# hexapod.net
KiCad netlist of a schematic drawn in EAGLE
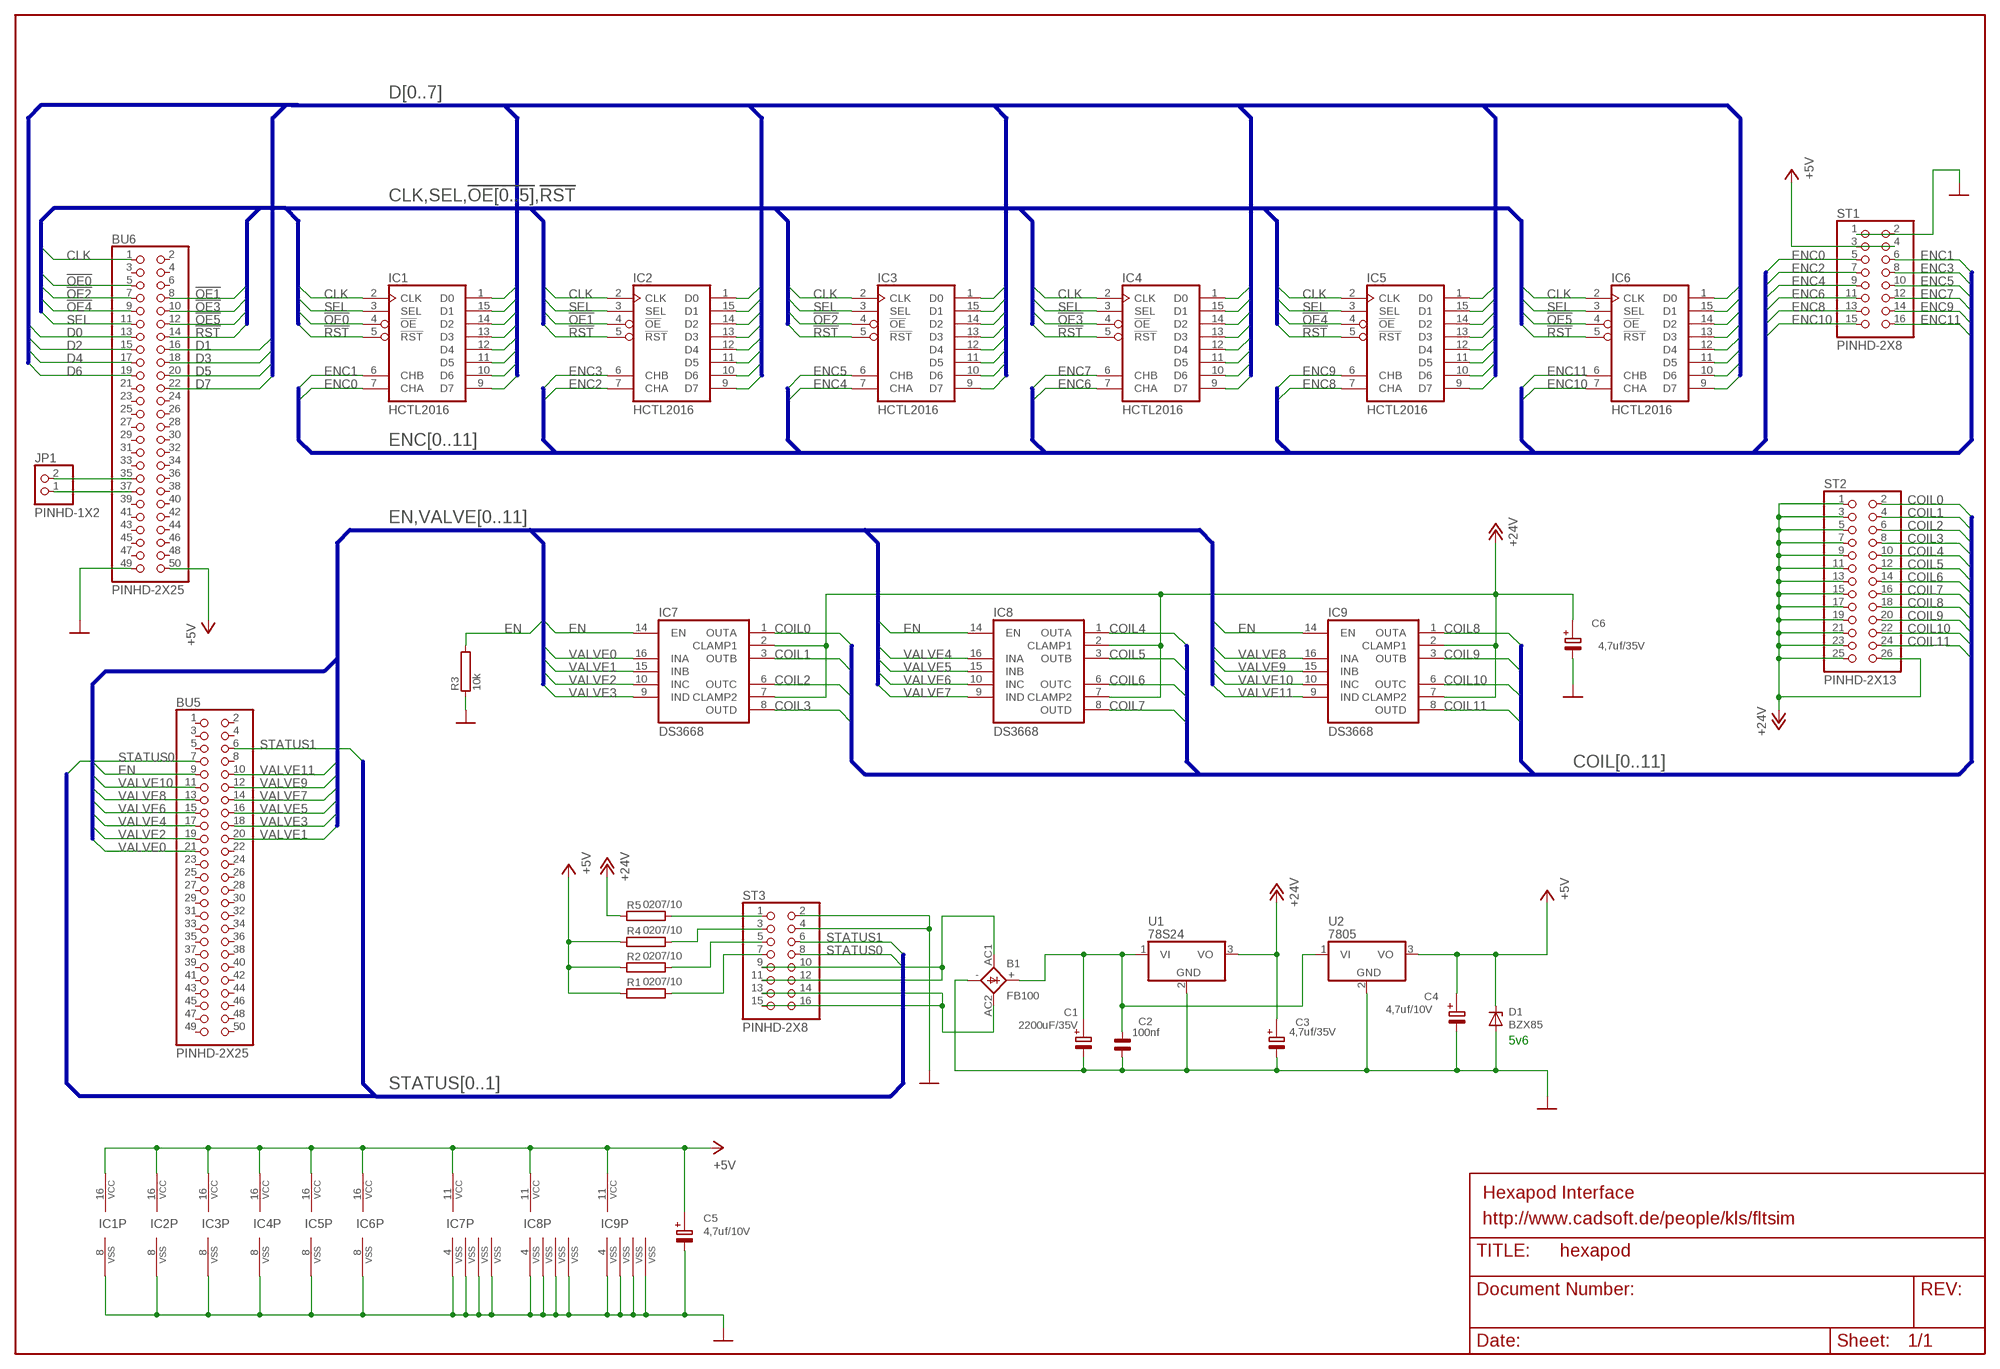
[diagram p0: schematic, sheet 1]

(export (version "E")
  (design (tool "Eeschema 10.0.6"))
  (components
    (comp (ref "B1")
      (value "FB100")
      (footprint "eagle-import:FB100")
      (libsource (lib "eagle-import") (part "FB100"))
    )
    (comp (ref "BU5")
      (value "PINHD-2X25")
      (footprint "eagle-import:2X25")
      (libsource (lib "eagle-import") (part "PINHD-2X25"))
    )
    (comp (ref "BU6")
      (value "PINHD-2X25")
      (footprint "eagle-import:2X25")
      (libsource (lib "eagle-import") (part "PINHD-2X25"))
    )
    (comp (ref "C1")
      (value "2200uF/35V")
      (footprint "eagle-import:E35-16")
      (libsource (lib "eagle-import") (part "E35-16"))
    )
    (comp (ref "C2")
      (value "100nf")
      (footprint "eagle-import:C5B2,5A")
      (libsource (lib "eagle-import") (part "C5B2,5A"))
    )
    (comp (ref "C3")
      (value "4,7uf/35V")
      (footprint "eagle-import:E2,5-5")
      (libsource (lib "eagle-import") (part "E2-5@1"))
    )
    (comp (ref "C4")
      (value "4,7uf/10V")
      (footprint "eagle-import:E2,5-5")
      (libsource (lib "eagle-import") (part "E2,5-5"))
    )
    (comp (ref "C5")
      (value "4,7uf/10V")
      (footprint "eagle-import:E2,5-5")
      (libsource (lib "eagle-import") (part "E2,5-5"))
    )
    (comp (ref "C6")
      (value "4,7uf/35V")
      (footprint "eagle-import:E2,5-5")
      (libsource (lib "eagle-import") (part "E2-5@1"))
    )
    (comp (ref "D1")
      (value "BZX85")
      (footprint "eagle-import:DO41Z10")
      (libsource (lib "eagle-import") (part "BZX85"))
    )
    (comp (ref "IC1")
      (value "HCTL2016")
      (footprint "eagle-import:DIL-16")
      (libsource (lib "eagle-import") (part "HCTL2016"))
    )
    (comp (ref "IC2")
      (value "HCTL2016")
      (footprint "eagle-import:DIL-16")
      (libsource (lib "eagle-import") (part "HCTL2016"))
    )
    (comp (ref "IC3")
      (value "HCTL2016")
      (footprint "eagle-import:DIL-16")
      (libsource (lib "eagle-import") (part "HCTL2016"))
    )
    (comp (ref "IC4")
      (value "HCTL2016")
      (footprint "eagle-import:DIL-16")
      (libsource (lib "eagle-import") (part "HCTL2016"))
    )
    (comp (ref "IC5")
      (value "HCTL2016")
      (footprint "eagle-import:DIL-16")
      (libsource (lib "eagle-import") (part "HCTL2016"))
    )
    (comp (ref "IC6")
      (value "HCTL2016")
      (footprint "eagle-import:DIL-16")
      (libsource (lib "eagle-import") (part "HCTL2016"))
    )
    (comp (ref "IC7")
      (value "DS3668")
      (footprint "eagle-import:DIL-16")
      (libsource (lib "eagle-import") (part "DS3668"))
    )
    (comp (ref "IC8")
      (value "DS3668")
      (footprint "eagle-import:DIL-16")
      (libsource (lib "eagle-import") (part "DS3668"))
    )
    (comp (ref "IC9")
      (value "DS3668")
      (footprint "eagle-import:DIL-16")
      (libsource (lib "eagle-import") (part "DS3668"))
    )
    (comp (ref "JP1")
      (value "PINHD-1X2")
      (footprint "eagle-import:1X02")
      (libsource (lib "eagle-import") (part "PINHD-1X2"))
    )
    (comp (ref "R1")
      (value "0207/10")
      (footprint "eagle-import:0207_10")
      (libsource (lib "eagle-import") (part "0207/10"))
    )
    (comp (ref "R2")
      (value "0207/10")
      (footprint "eagle-import:0207_10")
      (libsource (lib "eagle-import") (part "0207/10"))
    )
    (comp (ref "R3")
      (value "10k")
      (footprint "eagle-import:0207_10@1")
      (libsource (lib "eagle-import") (part "0207/10@1"))
    )
    (comp (ref "R4")
      (value "0207/10")
      (footprint "eagle-import:0207_10")
      (libsource (lib "eagle-import") (part "0207/10"))
    )
    (comp (ref "R5")
      (value "0207/10")
      (footprint "eagle-import:0207_10")
      (libsource (lib "eagle-import") (part "0207/10"))
    )
    (comp (ref "ST1")
      (value "PINHD-2X8")
      (footprint "eagle-import:ML16")
      (libsource (lib "eagle-import") (part "PINHD-2X8@1"))
    )
    (comp (ref "ST2")
      (value "PINHD-2X13")
      (footprint "eagle-import:ML26")
      (libsource (lib "eagle-import") (part "PINHD-2X13@1"))
    )
    (comp (ref "ST3")
      (value "PINHD-2X8")
      (footprint "eagle-import:ML16")
      (libsource (lib "eagle-import") (part "PINHD-2X8@1"))
    )
    (comp (ref "U1")
      (value "78S24")
      (footprint "eagle-import:TO220H")
      (libsource (lib "eagle-import") (part "78XXT"))
    )
    (comp (ref "U2")
      (value "7805")
      (footprint "eagle-import:TO220H")
      (libsource (lib "eagle-import") (part "78XXT"))
    )
  )
  (nets
    (net (code "13") (name "+5V") (class "Default")
      (node (ref "BU6") (pin "50") (pinfunction "50_50") (pintype "passive"))
      (node (ref "C4") (pin "+") (pinfunction "+_+") (pintype "passive"))
      (node (ref "C5") (pin "+") (pinfunction "+_+") (pintype "passive"))
      (node (ref "D1") (pin "K") (pinfunction "K_K") (pintype "passive"))
      (node (ref "IC1") (pin "16") (pinfunction "VCC_16") (pintype "power_in"))
      (node (ref "IC2") (pin "16") (pinfunction "VCC_16") (pintype "power_in"))
      (node (ref "IC3") (pin "16") (pinfunction "VCC_16") (pintype "power_in"))
      (node (ref "IC4") (pin "16") (pinfunction "VCC_16") (pintype "power_in"))
      (node (ref "IC5") (pin "16") (pinfunction "VCC_16") (pintype "power_in"))
      (node (ref "IC6") (pin "16") (pinfunction "VCC_16") (pintype "power_in"))
      (node (ref "IC7") (pin "11") (pinfunction "VCC_11") (pintype "power_in"))
      (node (ref "IC8") (pin "11") (pinfunction "VCC_11") (pintype "power_in"))
      (node (ref "IC9") (pin "11") (pinfunction "VCC_11") (pintype "power_in"))
      (node (ref "R1") (pin "1") (pinfunction "1_1") (pintype "passive"))
      (node (ref "R2") (pin "1") (pinfunction "1_1") (pintype "passive"))
      (node (ref "R4") (pin "1") (pinfunction "1_1") (pintype "passive"))
      (node (ref "ST1") (pin "3") (pinfunction "3_3") (pintype "passive"))
      (node (ref "ST1") (pin "4") (pinfunction "4_4") (pintype "passive"))
      (node (ref "U2") (pin "3") (pinfunction "VO_3") (pintype "output"))
    )
    (net (code "14") (name "+24V") (class "Default")
      (node (ref "C3") (pin "+") (pinfunction "+_+") (pintype "passive"))
      (node (ref "C6") (pin "+") (pinfunction "+_+") (pintype "passive"))
      (node (ref "IC7") (pin "2") (pinfunction "CLAMP1_2") (pintype "bidirectional"))
      (node (ref "IC7") (pin "7") (pinfunction "CLAMP2_7") (pintype "bidirectional"))
      (node (ref "IC8") (pin "2") (pinfunction "CLAMP1_2") (pintype "bidirectional"))
      (node (ref "IC8") (pin "7") (pinfunction "CLAMP2_7") (pintype "bidirectional"))
      (node (ref "IC9") (pin "2") (pinfunction "CLAMP1_2") (pintype "bidirectional"))
      (node (ref "IC9") (pin "7") (pinfunction "CLAMP2_7") (pintype "bidirectional"))
      (node (ref "R5") (pin "1") (pinfunction "1_1") (pintype "passive"))
      (node (ref "ST2") (pin "1") (pinfunction "1_1") (pintype "passive"))
      (node (ref "ST2") (pin "11") (pinfunction "11_11") (pintype "passive"))
      (node (ref "ST2") (pin "13") (pinfunction "13_13") (pintype "passive"))
      (node (ref "ST2") (pin "15") (pinfunction "15_15") (pintype "passive"))
      (node (ref "ST2") (pin "17") (pinfunction "17_17") (pintype "passive"))
      (node (ref "ST2") (pin "19") (pinfunction "19_19") (pintype "passive"))
      (node (ref "ST2") (pin "21") (pinfunction "21_21") (pintype "passive"))
      (node (ref "ST2") (pin "23") (pinfunction "23_23") (pintype "passive"))
      (node (ref "ST2") (pin "25") (pinfunction "25_25") (pintype "passive"))
      (node (ref "ST2") (pin "26") (pinfunction "26_26") (pintype "passive"))
      (node (ref "ST2") (pin "3") (pinfunction "3_3") (pintype "passive"))
      (node (ref "ST2") (pin "5") (pinfunction "5_5") (pintype "passive"))
      (node (ref "ST2") (pin "7") (pinfunction "7_7") (pintype "passive"))
      (node (ref "ST2") (pin "9") (pinfunction "9_9") (pintype "passive"))
      (node (ref "U1") (pin "3") (pinfunction "VO_3") (pintype "output"))
    )
    (net (code "15") (name "/CLK") (class "Default")
      (node (ref "BU6") (pin "1") (pinfunction "1_1") (pintype "passive"))
      (node (ref "IC1") (pin "2") (pinfunction "CLK_2") (pintype "input"))
      (node (ref "IC2") (pin "2") (pinfunction "CLK_2") (pintype "input"))
      (node (ref "IC3") (pin "2") (pinfunction "CLK_2") (pintype "input"))
      (node (ref "IC4") (pin "2") (pinfunction "CLK_2") (pintype "input"))
      (node (ref "IC5") (pin "2") (pinfunction "CLK_2") (pintype "input"))
      (node (ref "IC6") (pin "2") (pinfunction "CLK_2") (pintype "input"))
    )
    (net (code "16") (name "/COIL0") (class "Default")
      (node (ref "IC7") (pin "1") (pinfunction "OUTA_1") (pintype "bidirectional"))
      (node (ref "ST2") (pin "2") (pinfunction "2_2") (pintype "passive"))
    )
    (net (code "17") (name "/COIL1") (class "Default")
      (node (ref "IC7") (pin "3") (pinfunction "OUTB_3") (pintype "bidirectional"))
      (node (ref "ST2") (pin "4") (pinfunction "4_4") (pintype "passive"))
    )
    (net (code "18") (name "/COIL2") (class "Default")
      (node (ref "IC7") (pin "6") (pinfunction "OUTC_6") (pintype "bidirectional"))
      (node (ref "ST2") (pin "6") (pinfunction "6_6") (pintype "passive"))
    )
    (net (code "19") (name "/COIL3") (class "Default")
      (node (ref "IC7") (pin "8") (pinfunction "OUTD_8") (pintype "bidirectional"))
      (node (ref "ST2") (pin "8") (pinfunction "8_8") (pintype "passive"))
    )
    (net (code "20") (name "/COIL4") (class "Default")
      (node (ref "IC8") (pin "1") (pinfunction "OUTA_1") (pintype "bidirectional"))
      (node (ref "ST2") (pin "10") (pinfunction "10_10") (pintype "passive"))
    )
    (net (code "21") (name "/COIL5") (class "Default")
      (node (ref "IC8") (pin "3") (pinfunction "OUTB_3") (pintype "bidirectional"))
      (node (ref "ST2") (pin "12") (pinfunction "12_12") (pintype "passive"))
    )
    (net (code "22") (name "/COIL6") (class "Default")
      (node (ref "IC8") (pin "6") (pinfunction "OUTC_6") (pintype "bidirectional"))
      (node (ref "ST2") (pin "14") (pinfunction "14_14") (pintype "passive"))
    )
    (net (code "23") (name "/COIL7") (class "Default")
      (node (ref "IC8") (pin "8") (pinfunction "OUTD_8") (pintype "bidirectional"))
      (node (ref "ST2") (pin "16") (pinfunction "16_16") (pintype "passive"))
    )
    (net (code "24") (name "/COIL8") (class "Default")
      (node (ref "IC9") (pin "1") (pinfunction "OUTA_1") (pintype "bidirectional"))
      (node (ref "ST2") (pin "18") (pinfunction "18_18") (pintype "passive"))
    )
    (net (code "25") (name "/COIL9") (class "Default")
      (node (ref "IC9") (pin "3") (pinfunction "OUTB_3") (pintype "bidirectional"))
      (node (ref "ST2") (pin "20") (pinfunction "20_20") (pintype "passive"))
    )
    (net (code "26") (name "/COIL10") (class "Default")
      (node (ref "IC9") (pin "6") (pinfunction "OUTC_6") (pintype "bidirectional"))
      (node (ref "ST2") (pin "22") (pinfunction "22_22") (pintype "passive"))
    )
    (net (code "27") (name "/COIL11") (class "Default")
      (node (ref "IC9") (pin "8") (pinfunction "OUTD_8") (pintype "bidirectional"))
      (node (ref "ST2") (pin "24") (pinfunction "24_24") (pintype "passive"))
    )
    (net (code "29") (name "/D0") (class "Default")
      (node (ref "BU6") (pin "13") (pinfunction "13_13") (pintype "passive"))
      (node (ref "IC1") (pin "1") (pinfunction "D0_1") (pintype "output"))
      (node (ref "IC2") (pin "1") (pinfunction "D0_1") (pintype "output"))
      (node (ref "IC3") (pin "1") (pinfunction "D0_1") (pintype "output"))
      (node (ref "IC4") (pin "1") (pinfunction "D0_1") (pintype "output"))
      (node (ref "IC5") (pin "1") (pinfunction "D0_1") (pintype "output"))
      (node (ref "IC6") (pin "1") (pinfunction "D0_1") (pintype "output"))
    )
    (net (code "30") (name "/D1") (class "Default")
      (node (ref "BU6") (pin "16") (pinfunction "16_16") (pintype "passive"))
      (node (ref "IC1") (pin "15") (pinfunction "D1_15") (pintype "output"))
      (node (ref "IC2") (pin "15") (pinfunction "D1_15") (pintype "output"))
      (node (ref "IC3") (pin "15") (pinfunction "D1_15") (pintype "output"))
      (node (ref "IC4") (pin "15") (pinfunction "D1_15") (pintype "output"))
      (node (ref "IC5") (pin "15") (pinfunction "D1_15") (pintype "output"))
      (node (ref "IC6") (pin "15") (pinfunction "D1_15") (pintype "output"))
    )
    (net (code "31") (name "/D2") (class "Default")
      (node (ref "BU6") (pin "15") (pinfunction "15_15") (pintype "passive"))
      (node (ref "IC1") (pin "14") (pinfunction "D2_14") (pintype "output"))
      (node (ref "IC2") (pin "14") (pinfunction "D2_14") (pintype "output"))
      (node (ref "IC3") (pin "14") (pinfunction "D2_14") (pintype "output"))
      (node (ref "IC4") (pin "14") (pinfunction "D2_14") (pintype "output"))
      (node (ref "IC5") (pin "14") (pinfunction "D2_14") (pintype "output"))
      (node (ref "IC6") (pin "14") (pinfunction "D2_14") (pintype "output"))
    )
    (net (code "32") (name "/D3") (class "Default")
      (node (ref "BU6") (pin "18") (pinfunction "18_18") (pintype "passive"))
      (node (ref "IC1") (pin "13") (pinfunction "D3_13") (pintype "output"))
      (node (ref "IC2") (pin "13") (pinfunction "D3_13") (pintype "output"))
      (node (ref "IC3") (pin "13") (pinfunction "D3_13") (pintype "output"))
      (node (ref "IC4") (pin "13") (pinfunction "D3_13") (pintype "output"))
      (node (ref "IC5") (pin "13") (pinfunction "D3_13") (pintype "output"))
      (node (ref "IC6") (pin "13") (pinfunction "D3_13") (pintype "output"))
    )
    (net (code "33") (name "/D4") (class "Default")
      (node (ref "BU6") (pin "17") (pinfunction "17_17") (pintype "passive"))
      (node (ref "IC1") (pin "12") (pinfunction "D4_12") (pintype "output"))
      (node (ref "IC2") (pin "12") (pinfunction "D4_12") (pintype "output"))
      (node (ref "IC3") (pin "12") (pinfunction "D4_12") (pintype "output"))
      (node (ref "IC4") (pin "12") (pinfunction "D4_12") (pintype "output"))
      (node (ref "IC5") (pin "12") (pinfunction "D4_12") (pintype "output"))
      (node (ref "IC6") (pin "12") (pinfunction "D4_12") (pintype "output"))
    )
    (net (code "34") (name "/D5") (class "Default")
      (node (ref "BU6") (pin "20") (pinfunction "20_20") (pintype "passive"))
      (node (ref "IC1") (pin "11") (pinfunction "D5_11") (pintype "output"))
      (node (ref "IC2") (pin "11") (pinfunction "D5_11") (pintype "output"))
      (node (ref "IC3") (pin "11") (pinfunction "D5_11") (pintype "output"))
      (node (ref "IC4") (pin "11") (pinfunction "D5_11") (pintype "output"))
      (node (ref "IC5") (pin "11") (pinfunction "D5_11") (pintype "output"))
      (node (ref "IC6") (pin "11") (pinfunction "D5_11") (pintype "output"))
    )
    (net (code "35") (name "/D6") (class "Default")
      (node (ref "BU6") (pin "19") (pinfunction "19_19") (pintype "passive"))
      (node (ref "IC1") (pin "10") (pinfunction "D6_10") (pintype "output"))
      (node (ref "IC2") (pin "10") (pinfunction "D6_10") (pintype "output"))
      (node (ref "IC3") (pin "10") (pinfunction "D6_10") (pintype "output"))
      (node (ref "IC4") (pin "10") (pinfunction "D6_10") (pintype "output"))
      (node (ref "IC5") (pin "10") (pinfunction "D6_10") (pintype "output"))
      (node (ref "IC6") (pin "10") (pinfunction "D6_10") (pintype "output"))
    )
    (net (code "36") (name "/D7") (class "Default")
      (node (ref "BU6") (pin "22") (pinfunction "22_22") (pintype "passive"))
      (node (ref "IC1") (pin "9") (pinfunction "D7_9") (pintype "output"))
      (node (ref "IC2") (pin "9") (pinfunction "D7_9") (pintype "output"))
      (node (ref "IC3") (pin "9") (pinfunction "D7_9") (pintype "output"))
      (node (ref "IC4") (pin "9") (pinfunction "D7_9") (pintype "output"))
      (node (ref "IC5") (pin "9") (pinfunction "D7_9") (pintype "output"))
      (node (ref "IC6") (pin "9") (pinfunction "D7_9") (pintype "output"))
    )
    (net (code "38") (name "/EN") (class "Default")
      (node (ref "BU5") (pin "9") (pinfunction "9_9") (pintype "passive"))
      (node (ref "IC7") (pin "14") (pinfunction "EN_14") (pintype "input"))
      (node (ref "IC8") (pin "14") (pinfunction "EN_14") (pintype "input"))
      (node (ref "IC9") (pin "14") (pinfunction "EN_14") (pintype "input"))
      (node (ref "R3") (pin "2") (pinfunction "2_2") (pintype "passive"))
    )
    (net (code "40") (name "/ENC0") (class "Default")
      (node (ref "IC1") (pin "7") (pinfunction "CHA_7") (pintype "input"))
      (node (ref "ST1") (pin "5") (pinfunction "5_5") (pintype "passive"))
    )
    (net (code "41") (name "/ENC1") (class "Default")
      (node (ref "IC1") (pin "6") (pinfunction "CHB_6") (pintype "input"))
      (node (ref "ST1") (pin "6") (pinfunction "6_6") (pintype "passive"))
    )
    (net (code "42") (name "/ENC2") (class "Default")
      (node (ref "IC2") (pin "7") (pinfunction "CHA_7") (pintype "input"))
      (node (ref "ST1") (pin "7") (pinfunction "7_7") (pintype "passive"))
    )
    (net (code "43") (name "/ENC3") (class "Default")
      (node (ref "IC2") (pin "6") (pinfunction "CHB_6") (pintype "input"))
      (node (ref "ST1") (pin "8") (pinfunction "8_8") (pintype "passive"))
    )
    (net (code "44") (name "/ENC4") (class "Default")
      (node (ref "IC3") (pin "7") (pinfunction "CHA_7") (pintype "input"))
      (node (ref "ST1") (pin "9") (pinfunction "9_9") (pintype "passive"))
    )
    (net (code "45") (name "/ENC5") (class "Default")
      (node (ref "IC3") (pin "6") (pinfunction "CHB_6") (pintype "input"))
      (node (ref "ST1") (pin "10") (pinfunction "10_10") (pintype "passive"))
    )
    (net (code "46") (name "/ENC6") (class "Default")
      (node (ref "IC4") (pin "7") (pinfunction "CHA_7") (pintype "input"))
      (node (ref "ST1") (pin "11") (pinfunction "11_11") (pintype "passive"))
    )
    (net (code "47") (name "/ENC7") (class "Default")
      (node (ref "IC4") (pin "6") (pinfunction "CHB_6") (pintype "input"))
      (node (ref "ST1") (pin "12") (pinfunction "12_12") (pintype "passive"))
    )
    (net (code "48") (name "/ENC8") (class "Default")
      (node (ref "IC5") (pin "7") (pinfunction "CHA_7") (pintype "input"))
      (node (ref "ST1") (pin "13") (pinfunction "13_13") (pintype "passive"))
    )
    (net (code "49") (name "/ENC9") (class "Default")
      (node (ref "IC5") (pin "6") (pinfunction "CHB_6") (pintype "input"))
      (node (ref "ST1") (pin "14") (pinfunction "14_14") (pintype "passive"))
    )
    (net (code "50") (name "/ENC10") (class "Default")
      (node (ref "IC6") (pin "7") (pinfunction "CHA_7") (pintype "input"))
      (node (ref "ST1") (pin "15") (pinfunction "15_15") (pintype "passive"))
    )
    (net (code "51") (name "/ENC11") (class "Default")
      (node (ref "IC6") (pin "6") (pinfunction "CHB_6") (pintype "input"))
      (node (ref "ST1") (pin "16") (pinfunction "16_16") (pintype "passive"))
    )
    (net (code "53") (name "/SEL") (class "Default")
      (node (ref "BU6") (pin "11") (pinfunction "11_11") (pintype "passive"))
      (node (ref "IC1") (pin "3") (pinfunction "SEL_3") (pintype "input"))
      (node (ref "IC2") (pin "3") (pinfunction "SEL_3") (pintype "input"))
      (node (ref "IC3") (pin "3") (pinfunction "SEL_3") (pintype "input"))
      (node (ref "IC4") (pin "3") (pinfunction "SEL_3") (pintype "input"))
      (node (ref "IC5") (pin "3") (pinfunction "SEL_3") (pintype "input"))
      (node (ref "IC6") (pin "3") (pinfunction "SEL_3") (pintype "input"))
    )
    (net (code "54") (name "/STATUS0") (class "Default")
      (node (ref "BU5") (pin "7") (pinfunction "7_7") (pintype "passive"))
      (node (ref "ST3") (pin "8") (pinfunction "8_8") (pintype "passive"))
    )
    (net (code "55") (name "/STATUS1") (class "Default")
      (node (ref "BU5") (pin "6") (pinfunction "6_6") (pintype "passive"))
      (node (ref "ST3") (pin "6") (pinfunction "6_6") (pintype "passive"))
    )
    (net (code "57") (name "/VALVE0") (class "Default")
      (node (ref "BU5") (pin "21") (pinfunction "21_21") (pintype "passive"))
      (node (ref "IC7") (pin "16") (pinfunction "INA_16") (pintype "input"))
    )
    (net (code "58") (name "/VALVE1") (class "Default")
      (node (ref "BU5") (pin "20") (pinfunction "20_20") (pintype "passive"))
      (node (ref "IC7") (pin "15") (pinfunction "INB_15") (pintype "input"))
    )
    (net (code "59") (name "/VALVE2") (class "Default")
      (node (ref "BU5") (pin "19") (pinfunction "19_19") (pintype "passive"))
      (node (ref "IC7") (pin "10") (pinfunction "INC_10") (pintype "input"))
    )
    (net (code "60") (name "/VALVE3") (class "Default")
      (node (ref "BU5") (pin "18") (pinfunction "18_18") (pintype "passive"))
      (node (ref "IC7") (pin "9") (pinfunction "IND_9") (pintype "input"))
    )
    (net (code "61") (name "/VALVE4") (class "Default")
      (node (ref "BU5") (pin "17") (pinfunction "17_17") (pintype "passive"))
      (node (ref "IC8") (pin "16") (pinfunction "INA_16") (pintype "input"))
    )
    (net (code "62") (name "/VALVE5") (class "Default")
      (node (ref "BU5") (pin "16") (pinfunction "16_16") (pintype "passive"))
      (node (ref "IC8") (pin "15") (pinfunction "INB_15") (pintype "input"))
    )
    (net (code "63") (name "/VALVE6") (class "Default")
      (node (ref "BU5") (pin "15") (pinfunction "15_15") (pintype "passive"))
      (node (ref "IC8") (pin "10") (pinfunction "INC_10") (pintype "input"))
    )
    (net (code "64") (name "/VALVE7") (class "Default")
      (node (ref "BU5") (pin "14") (pinfunction "14_14") (pintype "passive"))
      (node (ref "IC8") (pin "9") (pinfunction "IND_9") (pintype "input"))
    )
    (net (code "65") (name "/VALVE8") (class "Default")
      (node (ref "BU5") (pin "13") (pinfunction "13_13") (pintype "passive"))
      (node (ref "IC9") (pin "16") (pinfunction "INA_16") (pintype "input"))
    )
    (net (code "66") (name "/VALVE9") (class "Default")
      (node (ref "BU5") (pin "12") (pinfunction "12_12") (pintype "passive"))
      (node (ref "IC9") (pin "15") (pinfunction "INB_15") (pintype "input"))
    )
    (net (code "67") (name "/VALVE10") (class "Default")
      (node (ref "BU5") (pin "11") (pinfunction "11_11") (pintype "passive"))
      (node (ref "IC9") (pin "10") (pinfunction "INC_10") (pintype "input"))
    )
    (net (code "68") (name "/VALVE11") (class "Default")
      (node (ref "BU5") (pin "10") (pinfunction "10_10") (pintype "passive"))
      (node (ref "IC9") (pin "9") (pinfunction "IND_9") (pintype "input"))
    )
    (net (code "70") (name "/~{OE0}") (class "Default")
      (node (ref "BU6") (pin "5") (pinfunction "5_5") (pintype "passive"))
      (node (ref "IC1") (pin "4") (pinfunction "~{OE}_4") (pintype "input"))
    )
    (net (code "71") (name "/~{OE1}") (class "Default")
      (node (ref "BU6") (pin "8") (pinfunction "8_8") (pintype "passive"))
      (node (ref "IC2") (pin "4") (pinfunction "~{OE}_4") (pintype "input"))
    )
    (net (code "72") (name "/~{OE2}") (class "Default")
      (node (ref "BU6") (pin "7") (pinfunction "7_7") (pintype "passive"))
      (node (ref "IC3") (pin "4") (pinfunction "~{OE}_4") (pintype "input"))
    )
    (net (code "73") (name "/~{OE3}") (class "Default")
      (node (ref "BU6") (pin "10") (pinfunction "10_10") (pintype "passive"))
      (node (ref "IC4") (pin "4") (pinfunction "~{OE}_4") (pintype "input"))
    )
    (net (code "74") (name "/~{OE4}") (class "Default")
      (node (ref "BU6") (pin "9") (pinfunction "9_9") (pintype "passive"))
      (node (ref "IC5") (pin "4") (pinfunction "~{OE}_4") (pintype "input"))
    )
    (net (code "75") (name "/~{OE5}") (class "Default")
      (node (ref "BU6") (pin "12") (pinfunction "12_12") (pintype "passive"))
      (node (ref "IC6") (pin "4") (pinfunction "~{OE}_4") (pintype "input"))
    )
    (net (code "76") (name "/~{RST}") (class "Default")
      (node (ref "BU6") (pin "14") (pinfunction "14_14") (pintype "passive"))
      (node (ref "IC1") (pin "5") (pinfunction "~{RST}_5") (pintype "input"))
      (node (ref "IC2") (pin "5") (pinfunction "~{RST}_5") (pintype "input"))
      (node (ref "IC3") (pin "5") (pinfunction "~{RST}_5") (pintype "input"))
      (node (ref "IC4") (pin "5") (pinfunction "~{RST}_5") (pintype "input"))
      (node (ref "IC5") (pin "5") (pinfunction "~{RST}_5") (pintype "input"))
      (node (ref "IC6") (pin "5") (pinfunction "~{RST}_5") (pintype "input"))
    )
    (net (code "77") (name "GND") (class "Default")
      (node (ref "B1") (pin "-") (pinfunction "-_-") (pintype "passive"))
      (node (ref "BU6") (pin "49") (pinfunction "49_49") (pintype "passive"))
      (node (ref "C1") (pin "-") (pinfunction "-_-") (pintype "passive"))
      (node (ref "C2") (pin "1") (pinfunction "1_1") (pintype "passive"))
      (node (ref "C3") (pin "-") (pinfunction "-_-") (pintype "passive"))
      (node (ref "C4") (pin "-") (pinfunction "-_-") (pintype "passive"))
      (node (ref "C5") (pin "-") (pinfunction "-_-") (pintype "passive"))
      (node (ref "C6") (pin "-") (pinfunction "-_-") (pintype "passive"))
      (node (ref "D1") (pin "A") (pinfunction "A_A") (pintype "passive"))
      (node (ref "IC1") (pin "8") (pinfunction "VSS_8") (pintype "power_in"))
      (node (ref "IC2") (pin "8") (pinfunction "VSS_8") (pintype "power_in"))
      (node (ref "IC3") (pin "8") (pinfunction "VSS_8") (pintype "power_in"))
      (node (ref "IC4") (pin "8") (pinfunction "VSS_8") (pintype "power_in"))
      (node (ref "IC5") (pin "8") (pinfunction "VSS_8") (pintype "power_in"))
      (node (ref "IC6") (pin "8") (pinfunction "VSS_8") (pintype "power_in"))
      (node (ref "IC7") (pin "12") (pinfunction "VSS_12") (pintype "power_in"))
      (node (ref "IC7") (pin "13") (pinfunction "VSS_13") (pintype "power_in"))
      (node (ref "IC7") (pin "4") (pinfunction "VSS_4") (pintype "power_in"))
      (node (ref "IC7") (pin "5") (pinfunction "VSS_5") (pintype "power_in"))
      (node (ref "IC8") (pin "12") (pinfunction "VSS_12") (pintype "power_in"))
      (node (ref "IC8") (pin "13") (pinfunction "VSS_13") (pintype "power_in"))
      (node (ref "IC8") (pin "4") (pinfunction "VSS_4") (pintype "power_in"))
      (node (ref "IC8") (pin "5") (pinfunction "VSS_5") (pintype "power_in"))
      (node (ref "IC9") (pin "12") (pinfunction "VSS_12") (pintype "power_in"))
      (node (ref "IC9") (pin "13") (pinfunction "VSS_13") (pintype "power_in"))
      (node (ref "IC9") (pin "4") (pinfunction "VSS_4") (pintype "power_in"))
      (node (ref "IC9") (pin "5") (pinfunction "VSS_5") (pintype "power_in"))
      (node (ref "R3") (pin "1") (pinfunction "1_1") (pintype "passive"))
      (node (ref "ST1") (pin "1") (pinfunction "1_1") (pintype "passive"))
      (node (ref "ST1") (pin "2") (pinfunction "2_2") (pintype "passive"))
      (node (ref "ST3") (pin "2") (pinfunction "2_2") (pintype "passive"))
      (node (ref "ST3") (pin "4") (pinfunction "4_4") (pintype "passive"))
      (node (ref "U1") (pin "2") (pinfunction "GND_2") (pintype "input"))
      (node (ref "U2") (pin "2") (pinfunction "GND_2") (pintype "input"))
    )
    (net (code "78") (name "Net-(B1-PadAC1)") (class "Default")
      (node (ref "B1") (pin "AC1") (pinfunction "AC1_AC1") (pintype "passive"))
      (node (ref "ST3") (pin "10") (pinfunction "10_10") (pintype "passive"))
      (node (ref "ST3") (pin "11") (pinfunction "11_11") (pintype "passive"))
      (node (ref "ST3") (pin "12") (pinfunction "12_12") (pintype "passive"))
      (node (ref "ST3") (pin "9") (pinfunction "9_9") (pintype "passive"))
    )
    (net (code "79") (name "Net-(B1-PadAC2)") (class "Default")
      (node (ref "B1") (pin "AC2") (pinfunction "AC2_AC2") (pintype "passive"))
      (node (ref "ST3") (pin "13") (pinfunction "13_13") (pintype "passive"))
      (node (ref "ST3") (pin "14") (pinfunction "14_14") (pintype "passive"))
      (node (ref "ST3") (pin "15") (pinfunction "15_15") (pintype "passive"))
      (node (ref "ST3") (pin "16") (pinfunction "16_16") (pintype "passive"))
    )
    (net (code "80") (name "Net-(BU6-Pad35)") (class "Default")
      (node (ref "BU6") (pin "35") (pinfunction "35_35") (pintype "passive"))
      (node (ref "JP1") (pin "2") (pinfunction "2_2") (pintype "passive"))
    )
    (net (code "81") (name "Net-(BU6-Pad37)") (class "Default")
      (node (ref "BU6") (pin "37") (pinfunction "37_37") (pintype "passive"))
      (node (ref "JP1") (pin "1") (pinfunction "1_1") (pintype "passive"))
    )
    (net (code "82") (name "Net-(R1-Pad2)") (class "Default")
      (node (ref "R1") (pin "2") (pinfunction "2_2") (pintype "passive"))
      (node (ref "ST3") (pin "7") (pinfunction "7_7") (pintype "passive"))
    )
    (net (code "83") (name "Net-(R2-Pad2)") (class "Default")
      (node (ref "R2") (pin "2") (pinfunction "2_2") (pintype "passive"))
      (node (ref "ST3") (pin "5") (pinfunction "5_5") (pintype "passive"))
    )
    (net (code "84") (name "Net-(R4-Pad2)") (class "Default")
      (node (ref "R4") (pin "2") (pinfunction "2_2") (pintype "passive"))
      (node (ref "ST3") (pin "3") (pinfunction "3_3") (pintype "passive"))
    )
    (net (code "85") (name "Net-(R5-Pad2)") (class "Default")
      (node (ref "R5") (pin "2") (pinfunction "2_2") (pintype "passive"))
      (node (ref "ST3") (pin "1") (pinfunction "1_1") (pintype "passive"))
    )
    (net (code "86") (name "Net-(U1-VI)") (class "Default")
      (node (ref "B1") (pin "+") (pinfunction "+_+") (pintype "passive"))
      (node (ref "C1") (pin "+") (pinfunction "+_+") (pintype "passive"))
      (node (ref "C2") (pin "2") (pinfunction "2_2") (pintype "passive"))
      (node (ref "U1") (pin "1") (pinfunction "VI_1") (pintype "input"))
      (node (ref "U2") (pin "1") (pinfunction "VI_1") (pintype "input"))
    )
    (net (code "87") (name "unconnected-(BU5-Pad1)") (class "Default")
      (node (ref "BU5") (pin "1") (pinfunction "1_1") (pintype "passive"))
    )
    (net (code "88") (name "unconnected-(BU5-Pad2)") (class "Default")
      (node (ref "BU5") (pin "2") (pinfunction "2_2") (pintype "passive"))
    )
    (net (code "89") (name "unconnected-(BU5-Pad3)") (class "Default")
      (node (ref "BU5") (pin "3") (pinfunction "3_3") (pintype "passive"))
    )
    (net (code "90") (name "unconnected-(BU5-Pad4)") (class "Default")
      (node (ref "BU5") (pin "4") (pinfunction "4_4") (pintype "passive"))
    )
    (net (code "91") (name "unconnected-(BU5-Pad5)") (class "Default")
      (node (ref "BU5") (pin "5") (pinfunction "5_5") (pintype "passive"))
    )
    (net (code "92") (name "unconnected-(BU5-Pad8)") (class "Default")
      (node (ref "BU5") (pin "8") (pinfunction "8_8") (pintype "passive"))
    )
    (net (code "93") (name "unconnected-(BU5-Pad22)") (class "Default")
      (node (ref "BU5") (pin "22") (pinfunction "22_22") (pintype "passive"))
    )
    (net (code "94") (name "unconnected-(BU5-Pad23)") (class "Default")
      (node (ref "BU5") (pin "23") (pinfunction "23_23") (pintype "passive"))
    )
    (net (code "95") (name "unconnected-(BU5-Pad24)") (class "Default")
      (node (ref "BU5") (pin "24") (pinfunction "24_24") (pintype "passive"))
    )
    (net (code "96") (name "unconnected-(BU5-Pad25)") (class "Default")
      (node (ref "BU5") (pin "25") (pinfunction "25_25") (pintype "passive"))
    )
    (net (code "97") (name "unconnected-(BU5-Pad26)") (class "Default")
      (node (ref "BU5") (pin "26") (pinfunction "26_26") (pintype "passive"))
    )
    (net (code "98") (name "unconnected-(BU5-Pad27)") (class "Default")
      (node (ref "BU5") (pin "27") (pinfunction "27_27") (pintype "passive"))
    )
    (net (code "99") (name "unconnected-(BU5-Pad28)") (class "Default")
      (node (ref "BU5") (pin "28") (pinfunction "28_28") (pintype "passive"))
    )
    (net (code "100") (name "unconnected-(BU5-Pad29)") (class "Default")
      (node (ref "BU5") (pin "29") (pinfunction "29_29") (pintype "passive"))
    )
    (net (code "101") (name "unconnected-(BU5-Pad30)") (class "Default")
      (node (ref "BU5") (pin "30") (pinfunction "30_30") (pintype "passive"))
    )
    (net (code "102") (name "unconnected-(BU5-Pad31)") (class "Default")
      (node (ref "BU5") (pin "31") (pinfunction "31_31") (pintype "passive"))
    )
    (net (code "103") (name "unconnected-(BU5-Pad32)") (class "Default")
      (node (ref "BU5") (pin "32") (pinfunction "32_32") (pintype "passive"))
    )
    (net (code "104") (name "unconnected-(BU5-Pad33)") (class "Default")
      (node (ref "BU5") (pin "33") (pinfunction "33_33") (pintype "passive"))
    )
    (net (code "105") (name "unconnected-(BU5-Pad34)") (class "Default")
      (node (ref "BU5") (pin "34") (pinfunction "34_34") (pintype "passive"))
    )
    (net (code "106") (name "unconnected-(BU5-Pad35)") (class "Default")
      (node (ref "BU5") (pin "35") (pinfunction "35_35") (pintype "passive"))
    )
    (net (code "107") (name "unconnected-(BU5-Pad36)") (class "Default")
      (node (ref "BU5") (pin "36") (pinfunction "36_36") (pintype "passive"))
    )
    (net (code "108") (name "unconnected-(BU5-Pad37)") (class "Default")
      (node (ref "BU5") (pin "37") (pinfunction "37_37") (pintype "passive"))
    )
    (net (code "109") (name "unconnected-(BU5-Pad38)") (class "Default")
      (node (ref "BU5") (pin "38") (pinfunction "38_38") (pintype "passive"))
    )
    (net (code "110") (name "unconnected-(BU5-Pad39)") (class "Default")
      (node (ref "BU5") (pin "39") (pinfunction "39_39") (pintype "passive"))
    )
    (net (code "111") (name "unconnected-(BU5-Pad40)") (class "Default")
      (node (ref "BU5") (pin "40") (pinfunction "40_40") (pintype "passive"))
    )
    (net (code "112") (name "unconnected-(BU5-Pad41)") (class "Default")
      (node (ref "BU5") (pin "41") (pinfunction "41_41") (pintype "passive"))
    )
    (net (code "113") (name "unconnected-(BU5-Pad42)") (class "Default")
      (node (ref "BU5") (pin "42") (pinfunction "42_42") (pintype "passive"))
    )
    (net (code "114") (name "unconnected-(BU5-Pad43)") (class "Default")
      (node (ref "BU5") (pin "43") (pinfunction "43_43") (pintype "passive"))
    )
    (net (code "115") (name "unconnected-(BU5-Pad44)") (class "Default")
      (node (ref "BU5") (pin "44") (pinfunction "44_44") (pintype "passive"))
    )
    (net (code "116") (name "unconnected-(BU5-Pad45)") (class "Default")
      (node (ref "BU5") (pin "45") (pinfunction "45_45") (pintype "passive"))
    )
    (net (code "117") (name "unconnected-(BU5-Pad46)") (class "Default")
      (node (ref "BU5") (pin "46") (pinfunction "46_46") (pintype "passive"))
    )
    (net (code "118") (name "unconnected-(BU5-Pad47)") (class "Default")
      (node (ref "BU5") (pin "47") (pinfunction "47_47") (pintype "passive"))
    )
    (net (code "119") (name "unconnected-(BU5-Pad48)") (class "Default")
      (node (ref "BU5") (pin "48") (pinfunction "48_48") (pintype "passive"))
    )
    (net (code "120") (name "unconnected-(BU5-Pad49)") (class "Default")
      (node (ref "BU5") (pin "49") (pinfunction "49_49") (pintype "passive"))
    )
    (net (code "121") (name "unconnected-(BU5-Pad50)") (class "Default")
      (node (ref "BU5") (pin "50") (pinfunction "50_50") (pintype "passive"))
    )
    (net (code "122") (name "unconnected-(BU6-Pad2)") (class "Default")
      (node (ref "BU6") (pin "2") (pinfunction "2_2") (pintype "passive"))
    )
    (net (code "123") (name "unconnected-(BU6-Pad3)") (class "Default")
      (node (ref "BU6") (pin "3") (pinfunction "3_3") (pintype "passive"))
    )
    (net (code "124") (name "unconnected-(BU6-Pad4)") (class "Default")
      (node (ref "BU6") (pin "4") (pinfunction "4_4") (pintype "passive"))
    )
    (net (code "125") (name "unconnected-(BU6-Pad6)") (class "Default")
      (node (ref "BU6") (pin "6") (pinfunction "6_6") (pintype "passive"))
    )
    (net (code "126") (name "unconnected-(BU6-Pad21)") (class "Default")
      (node (ref "BU6") (pin "21") (pinfunction "21_21") (pintype "passive"))
    )
    (net (code "127") (name "unconnected-(BU6-Pad23)") (class "Default")
      (node (ref "BU6") (pin "23") (pinfunction "23_23") (pintype "passive"))
    )
    (net (code "128") (name "unconnected-(BU6-Pad24)") (class "Default")
      (node (ref "BU6") (pin "24") (pinfunction "24_24") (pintype "passive"))
    )
    (net (code "129") (name "unconnected-(BU6-Pad25)") (class "Default")
      (node (ref "BU6") (pin "25") (pinfunction "25_25") (pintype "passive"))
    )
    (net (code "130") (name "unconnected-(BU6-Pad26)") (class "Default")
      (node (ref "BU6") (pin "26") (pinfunction "26_26") (pintype "passive"))
    )
    (net (code "131") (name "unconnected-(BU6-Pad27)") (class "Default")
      (node (ref "BU6") (pin "27") (pinfunction "27_27") (pintype "passive"))
    )
    (net (code "132") (name "unconnected-(BU6-Pad28)") (class "Default")
      (node (ref "BU6") (pin "28") (pinfunction "28_28") (pintype "passive"))
    )
    (net (code "133") (name "unconnected-(BU6-Pad29)") (class "Default")
      (node (ref "BU6") (pin "29") (pinfunction "29_29") (pintype "passive"))
    )
    (net (code "134") (name "unconnected-(BU6-Pad30)") (class "Default")
      (node (ref "BU6") (pin "30") (pinfunction "30_30") (pintype "passive"))
    )
    (net (code "135") (name "unconnected-(BU6-Pad31)") (class "Default")
      (node (ref "BU6") (pin "31") (pinfunction "31_31") (pintype "passive"))
    )
    (net (code "136") (name "unconnected-(BU6-Pad32)") (class "Default")
      (node (ref "BU6") (pin "32") (pinfunction "32_32") (pintype "passive"))
    )
    (net (code "137") (name "unconnected-(BU6-Pad33)") (class "Default")
      (node (ref "BU6") (pin "33") (pinfunction "33_33") (pintype "passive"))
    )
    (net (code "138") (name "unconnected-(BU6-Pad34)") (class "Default")
      (node (ref "BU6") (pin "34") (pinfunction "34_34") (pintype "passive"))
    )
    (net (code "139") (name "unconnected-(BU6-Pad36)") (class "Default")
      (node (ref "BU6") (pin "36") (pinfunction "36_36") (pintype "passive"))
    )
    (net (code "140") (name "unconnected-(BU6-Pad38)") (class "Default")
      (node (ref "BU6") (pin "38") (pinfunction "38_38") (pintype "passive"))
    )
    (net (code "141") (name "unconnected-(BU6-Pad39)") (class "Default")
      (node (ref "BU6") (pin "39") (pinfunction "39_39") (pintype "passive"))
    )
    (net (code "142") (name "unconnected-(BU6-Pad40)") (class "Default")
      (node (ref "BU6") (pin "40") (pinfunction "40_40") (pintype "passive"))
    )
    (net (code "143") (name "unconnected-(BU6-Pad41)") (class "Default")
      (node (ref "BU6") (pin "41") (pinfunction "41_41") (pintype "passive"))
    )
    (net (code "144") (name "unconnected-(BU6-Pad42)") (class "Default")
      (node (ref "BU6") (pin "42") (pinfunction "42_42") (pintype "passive"))
    )
    (net (code "145") (name "unconnected-(BU6-Pad43)") (class "Default")
      (node (ref "BU6") (pin "43") (pinfunction "43_43") (pintype "passive"))
    )
    (net (code "146") (name "unconnected-(BU6-Pad44)") (class "Default")
      (node (ref "BU6") (pin "44") (pinfunction "44_44") (pintype "passive"))
    )
    (net (code "147") (name "unconnected-(BU6-Pad45)") (class "Default")
      (node (ref "BU6") (pin "45") (pinfunction "45_45") (pintype "passive"))
    )
    (net (code "148") (name "unconnected-(BU6-Pad46)") (class "Default")
      (node (ref "BU6") (pin "46") (pinfunction "46_46") (pintype "passive"))
    )
    (net (code "149") (name "unconnected-(BU6-Pad47)") (class "Default")
      (node (ref "BU6") (pin "47") (pinfunction "47_47") (pintype "passive"))
    )
    (net (code "150") (name "unconnected-(BU6-Pad48)") (class "Default")
      (node (ref "BU6") (pin "48") (pinfunction "48_48") (pintype "passive"))
    )
  )
)
